# PowerOutput_Switch.net
KiCad netlist of a schematic drawn in Altium Designer
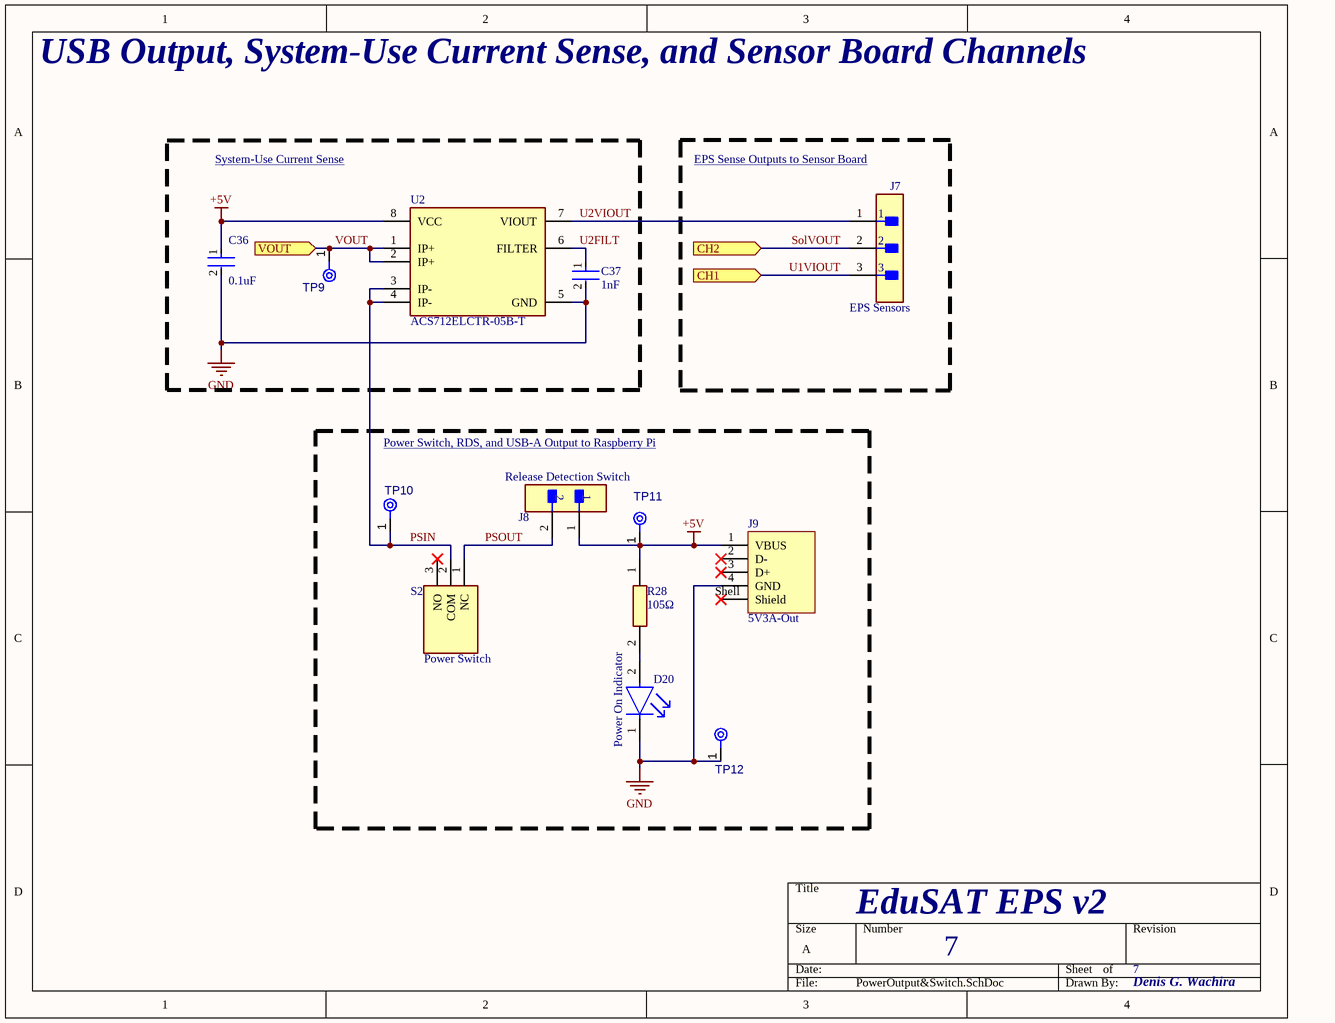
[diagram p0: PowerOutput&Switch.SchDoc]

(export (version "E")
  (design (tool "Eeschema 10.0.6"))
  (components
    (comp (ref "C36")
      (value "0.1uF")
      (footprint "FP-CL21-IPC_A")
      (description "50V 0.1uF X7R ±10% 0805 Multilayer Ceramic Capacitors MLCC - SMD/SMT ROHS TCC0805X7R104K500DT")
      (fields (field (name "TOLERANCE") "10%"))
      (libsource (lib "Altium Content Vault") (part "b4654b650e69147ec39a6b967a45e02"))
    )
    (comp (ref "C37")
      (value "1nF")
      (footprint "FP-CL21-IPC_B")
      (fields (field (name "TOLERANCE") "10%") (field (name "VOLTAGE") "50V"))
      (libsource (lib "Altium Content Vault") (part "b4654b650e69147ec39a6b967a45e02"))
    )
    (comp (ref "D20")
      (value "Power On Indicator")
      (footprint "FP-LTST-C170GKT-MFG")
      (description "LED GREEN CLEAR SMD KT-0805G")
      (fields (field (name "VOLTAGE") "5V"))
      (libsource (lib "Altium Content Vault") (part "8706943c75ba83719d021d2fdc84c58"))
    )
    (comp (ref "J7")
      (value "EPS Sensors")
      (footprint "FP-S3B-XH-A-1_LF_SN-MFG")
      (description "CONN HEADER R/A 3POS 2.5MM \r\nHCZZ0139-3")
      (libsource (lib "Altium Content Vault") (part "0d3f023dd272f625e17a2be33dea85f"))
    )
    (comp (ref "J8")
      (value "Release Detection Switch")
      (footprint "FP-S2B-XH-A-1_LF_SN-MFG")
      (description "CONN HEADER R/A 2POS 2.5MM HCZZ0139-2")
      (libsource (lib "Altium Content Vault") (part "3bc925449376181038e59eaffc5286c"))
    )
    (comp (ref "J9")
      (value "5V3A-Out")
      (footprint "614004135023")
      (description "USB 2.0 3A 1 Straight 4P Female -55℃~+85℃ Type-A Plugin USB Connectors ROHS\r\n916-252A1113Y10210")
      (libsource (lib "Altium Content Vault") (part "USB 2.0_Type A_Receptacle_1 Port"))
    )
    (comp (ref "R28")
      (value "105Ω")
      (footprint "SamacSys:RESC2012X65N")
      (fields (field (name "MANUFACTURER_PART_NUMBER") "AECR0805F27R0K9"))
      (libsource (lib "*") (part "AECR0805F27R0K9"))
    )
    (comp (ref "S2")
      (value "Power Switch")
      (footprint "SamacSys:SS12D10L3")
      (description "Switch")
      (fields (field (name "MANUFACTURER_PART_NUMBER") "SS-12D10L3"))
      (libsource (lib "*") (part "SS-12D10L3"))
    )
    (comp (ref "TP9")
      (value "TPAD6R")
      (footprint "TP06R")
      (description "0.6mm round")
      (libsource (lib "University of Nairobi") (part "CMP-001-0001-4"))
    )
    (comp (ref "TP10")
      (value "TPAD6R")
      (footprint "TP06R")
      (description "0.6mm round")
      (libsource (lib "University of Nairobi") (part "CMP-001-0001-4"))
    )
    (comp (ref "TP11")
      (value "TPAD6R")
      (footprint "TP06R")
      (description "0.6mm round")
      (libsource (lib "University of Nairobi") (part "CMP-001-0001-4"))
    )
    (comp (ref "TP12")
      (value "TPAD6R")
      (footprint "TP06R")
      (description "0.6mm round")
      (libsource (lib "University of Nairobi") (part "CMP-001-0001-4"))
    )
    (comp (ref "U2")
      (value "ACS712ELCTR-05B-T")
      (footprint "FP-LC-8-IPC_A")
      (description "SENSOR CURRENT HALL 5A AC/DC")
      (fields (field (name "VOLTAGE") "5V"))
      (libsource (lib "Altium Content Vault") (part "160a4736de78720bdb7fdad13a6f0ac"))
    )
  )
  (nets
    (net (code "1") (name "+5V") (class "Default")
      (node (ref "C36") (pin "1") (pinfunction "1_1") (pintype "passive"))
      (node (ref "J8") (pin "1") (pinfunction "1_1") (pintype "passive"))
      (node (ref "J9") (pin "1") (pinfunction "VBUS_1") (pintype "passive"))
      (node (ref "R28") (pin "1") (pinfunction "1_1") (pintype "passive"))
      (node (ref "TP11") (pin "1") (pinfunction "TP_1") (pintype "passive"))
      (node (ref "U2") (pin "8") (pinfunction "VCC_8") (pintype "power_in"))
    )
    (net (code "2") (name "/PSIN") (class "Default")
      (node (ref "S2") (pin "2") (pinfunction "COM_2") (pintype "passive"))
      (node (ref "TP10") (pin "1") (pinfunction "TP_1") (pintype "passive"))
      (node (ref "U2") (pin "3") (pinfunction "IP-_3") (pintype "passive"))
      (node (ref "U2") (pin "4") (pinfunction "IP-_4") (pintype "passive"))
    )
    (net (code "3") (name "/PSOUT") (class "Default")
      (node (ref "J8") (pin "2") (pinfunction "2_2") (pintype "passive"))
      (node (ref "S2") (pin "1") (pinfunction "NC_1") (pintype "passive"))
    )
    (net (code "4") (name "/SolVOUT") (class "Default")
      (node (ref "J7") (pin "2") (pinfunction "2_2") (pintype "passive"))
    )
    (net (code "5") (name "/U1VIOUT") (class "Default")
      (node (ref "J7") (pin "3") (pinfunction "3_3") (pintype "passive"))
    )
    (net (code "6") (name "/U2FILT") (class "Default")
      (node (ref "C37") (pin "1") (pinfunction "1_1") (pintype "passive"))
      (node (ref "U2") (pin "6") (pinfunction "FILTER_6") (pintype "passive"))
    )
    (net (code "7") (name "/U2VIOUT") (class "Default")
      (node (ref "J7") (pin "1") (pinfunction "1_1") (pintype "passive"))
      (node (ref "U2") (pin "7") (pinfunction "VIOUT_7") (pintype "passive"))
    )
    (net (code "8") (name "/VOUT") (class "Default")
      (node (ref "TP9") (pin "1") (pinfunction "TP_1") (pintype "passive"))
      (node (ref "U2") (pin "1") (pinfunction "IP+_1") (pintype "passive"))
      (node (ref "U2") (pin "2") (pinfunction "IP+_2") (pintype "passive"))
    )
    (net (code "9") (name "GND") (class "Default")
      (node (ref "C36") (pin "2") (pinfunction "2_2") (pintype "passive"))
      (node (ref "C37") (pin "2") (pinfunction "2_2") (pintype "passive"))
      (node (ref "D20") (pin "1") (pinfunction "C_1") (pintype "passive"))
      (node (ref "J9") (pin "4") (pinfunction "GND_4") (pintype "passive"))
      (node (ref "TP12") (pin "1") (pinfunction "TP_1") (pintype "passive"))
      (node (ref "U2") (pin "5") (pinfunction "GND_5") (pintype "power_in"))
    )
    (net (code "10") (name "Net-(D20-A)") (class "Default")
      (node (ref "D20") (pin "2") (pinfunction "A_2") (pintype "passive"))
      (node (ref "R28") (pin "2") (pinfunction "2_2") (pintype "passive"))
    )
    (net (code "11") (name "unconnected-(J9-D+-Pad3)") (class "Default")
      (node (ref "J9") (pin "3") (pinfunction "D+_3") (pintype "passive+no_connect"))
    )
    (net (code "12") (name "unconnected-(J9-D--Pad2)") (class "Default")
      (node (ref "J9") (pin "2") (pinfunction "D-_2") (pintype "passive+no_connect"))
    )
    (net (code "13") (name "unconnected-(J9-Shield-PadShell)") (class "Default")
      (node (ref "J9") (pin "Shell") (pinfunction "Shield_Shell") (pintype "passive+no_connect"))
    )
    (net (code "14") (name "unconnected-(S2-NO-Pad3)") (class "Default")
      (node (ref "S2") (pin "3") (pinfunction "NO_3") (pintype "passive+no_connect"))
    )
  )
)
